# ML8511_breakout.net
KiCad netlist of a schematic drawn in EAGLE
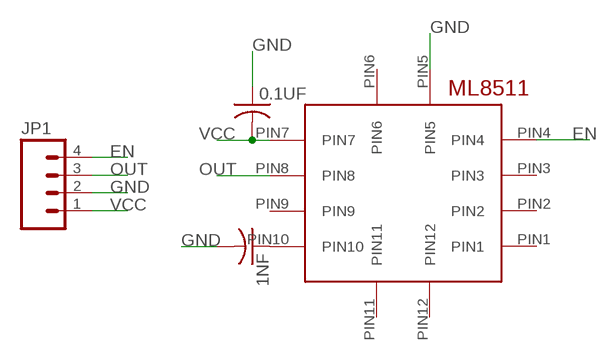
[diagram p0: schematic, sheet 1]

(export (version "E")
  (design (tool "Eeschema 10.0.6"))
  (components
    (comp (ref "0.1UF")
      (value "C-USC0603")
      (footprint "eagle-import:C0603")
      (libsource (lib "eagle-import") (part "C-USC0603"))
    )
    (comp (ref "1NF")
      (value "C-USC0603")
      (footprint "eagle-import:C0603")
      (libsource (lib "eagle-import") (part "C-USC0603"))
    )
    (comp (ref "JP1")
      (value "M04PTH")
      (footprint "eagle-import:1X04")
      (libsource (lib "eagle-import") (part "M04PTH"))
    )
    (comp (ref "U$1")
      (value "ML8511")
      (footprint "eagle-import:ML8511")
      (libsource (lib "eagle-import") (part "ML8511"))
    )
  )
  (nets
    (net (code "1") (name "/EN") (class "Default")
      (node (ref "JP1") (pin "4") (pinfunction "4_4") (pintype "passive"))
      (node (ref "U$1") (pin "PIN4") (pinfunction "PIN4_PIN4") (pintype "bidirectional"))
    )
    (net (code "2") (name "/GND") (class "Default")
      (node (ref "0.1UF") (pin "1") (pinfunction "1_1") (pintype "passive"))
      (node (ref "1NF") (pin "2") (pinfunction "2_2") (pintype "passive"))
      (node (ref "JP1") (pin "2") (pinfunction "2_2") (pintype "passive"))
      (node (ref "U$1") (pin "PIN5") (pinfunction "PIN5_PIN5") (pintype "bidirectional"))
    )
    (net (code "3") (name "/OUT") (class "Default")
      (node (ref "JP1") (pin "3") (pinfunction "3_3") (pintype "passive"))
      (node (ref "U$1") (pin "PIN8") (pinfunction "PIN8_PIN8") (pintype "bidirectional"))
    )
    (net (code "4") (name "/VCC") (class "Default")
      (node (ref "0.1UF") (pin "2") (pinfunction "2_2") (pintype "passive"))
      (node (ref "JP1") (pin "1") (pinfunction "1_1") (pintype "passive"))
      (node (ref "U$1") (pin "PIN7") (pinfunction "PIN7_PIN7") (pintype "bidirectional"))
    )
    (net (code "5") (name "Net-(1NF-Pad1)") (class "Default")
      (node (ref "1NF") (pin "1") (pinfunction "1_1") (pintype "passive"))
      (node (ref "U$1") (pin "PIN10") (pinfunction "PIN10_PIN10") (pintype "bidirectional"))
    )
    (net (code "6") (name "unconnected-(U$1-PadPIN1)") (class "Default")
      (node (ref "U$1") (pin "PIN1") (pinfunction "PIN1_PIN1") (pintype "bidirectional"))
    )
    (net (code "7") (name "unconnected-(U$1-PadPIN2)") (class "Default")
      (node (ref "U$1") (pin "PIN2") (pinfunction "PIN2_PIN2") (pintype "bidirectional"))
    )
    (net (code "8") (name "unconnected-(U$1-PadPIN3)") (class "Default")
      (node (ref "U$1") (pin "PIN3") (pinfunction "PIN3_PIN3") (pintype "bidirectional"))
    )
    (net (code "9") (name "unconnected-(U$1-PadPIN6)") (class "Default")
      (node (ref "U$1") (pin "PIN6") (pinfunction "PIN6_PIN6") (pintype "bidirectional"))
    )
    (net (code "10") (name "unconnected-(U$1-PadPIN9)") (class "Default")
      (node (ref "U$1") (pin "PIN9") (pinfunction "PIN9_PIN9") (pintype "bidirectional"))
    )
    (net (code "11") (name "unconnected-(U$1-PadPIN11)") (class "Default")
      (node (ref "U$1") (pin "PIN11") (pinfunction "PIN11_PIN11") (pintype "bidirectional"))
    )
    (net (code "12") (name "unconnected-(U$1-PadPIN12)") (class "Default")
      (node (ref "U$1") (pin "PIN12") (pinfunction "PIN12_PIN12") (pintype "bidirectional"))
    )
  )
)
